# UnicornPin.net
KiCad netlist of a schematic drawn in EAGLE
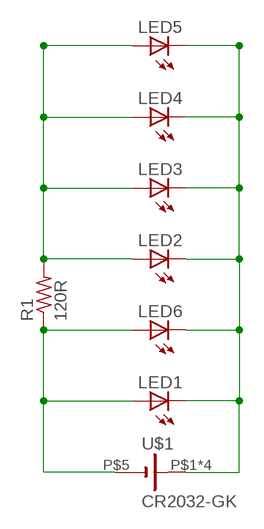
[diagram p0: schematic, sheet 1]

(export (version "E")
  (design (tool "Eeschema 10.0.6"))
  (components
    (comp (ref "LED1")
      (value "LED5MM")
      (footprint "eagle-import:LED5MM")
      (libsource (lib "eagle-import") (part "LED5MM"))
    )
    (comp (ref "LED2")
      (value "LED3MM")
      (footprint "eagle-import:LED3MM")
      (libsource (lib "eagle-import") (part "LED3MM"))
    )
    (comp (ref "LED3")
      (value "LED3MM")
      (footprint "eagle-import:LED3MM")
      (libsource (lib "eagle-import") (part "LED3MM"))
    )
    (comp (ref "LED4")
      (value "LED3MM")
      (footprint "eagle-import:LED3MM")
      (libsource (lib "eagle-import") (part "LED3MM"))
    )
    (comp (ref "LED5")
      (value "LED3MM")
      (footprint "eagle-import:LED3MM")
      (libsource (lib "eagle-import") (part "LED3MM"))
    )
    (comp (ref "LED6")
      (value "LED5MM")
      (footprint "eagle-import:LED5MM")
      (libsource (lib "eagle-import") (part "LED5MM"))
    )
    (comp (ref "R1")
      (value "120R")
      (footprint "eagle-import:0207_7")
      (libsource (lib "eagle-import") (part "R-US_0207/7"))
    )
    (comp (ref "U$1")
      (value "CR2032-GK")
      (footprint "eagle-import:BAT-HLD-001-THM")
      (libsource (lib "eagle-import") (part "CR2032-GK"))
    )
  )
  (nets
    (net (code "1") (name "Net-(LED1-C)") (class "Default")
      (node (ref "LED1") (pin "K") (pinfunction "C_K") (pintype "passive"))
      (node (ref "LED2") (pin "K") (pinfunction "C_K") (pintype "passive"))
      (node (ref "LED3") (pin "K") (pinfunction "C_K") (pintype "passive"))
      (node (ref "LED4") (pin "K") (pinfunction "C_K") (pintype "passive"))
      (node (ref "LED5") (pin "K") (pinfunction "C_K") (pintype "passive"))
      (node (ref "LED6") (pin "K") (pinfunction "C_K") (pintype "passive"))
      (node (ref "U$1") (pin "P$1") (pinfunction "+_P$1") (pintype "passive"))
      (node (ref "U$1") (pin "P$2") (pinfunction "+_P$2") (pintype "passive"))
      (node (ref "U$1") (pin "P$3") (pinfunction "+_P$3") (pintype "passive"))
      (node (ref "U$1") (pin "P$4") (pinfunction "+_P$4") (pintype "passive"))
    )
    (net (code "2") (name "Net-(LED2-PadA)") (class "Default")
      (node (ref "LED2") (pin "A") (pinfunction "A_A") (pintype "passive"))
      (node (ref "LED3") (pin "A") (pinfunction "A_A") (pintype "passive"))
      (node (ref "LED4") (pin "A") (pinfunction "A_A") (pintype "passive"))
      (node (ref "LED5") (pin "A") (pinfunction "A_A") (pintype "passive"))
      (node (ref "R1") (pin "2") (pinfunction "2_2") (pintype "passive"))
    )
    (net (code "3") (name "Net-(U$1--)") (class "Default")
      (node (ref "LED1") (pin "A") (pinfunction "A_A") (pintype "passive"))
      (node (ref "LED6") (pin "A") (pinfunction "A_A") (pintype "passive"))
      (node (ref "R1") (pin "1") (pinfunction "1_1") (pintype "passive"))
      (node (ref "U$1") (pin "P$5") (pinfunction "-_P$5") (pintype "passive"))
    )
  )
)
